# mega.net
KiCad netlist of a schematic drawn in EAGLE
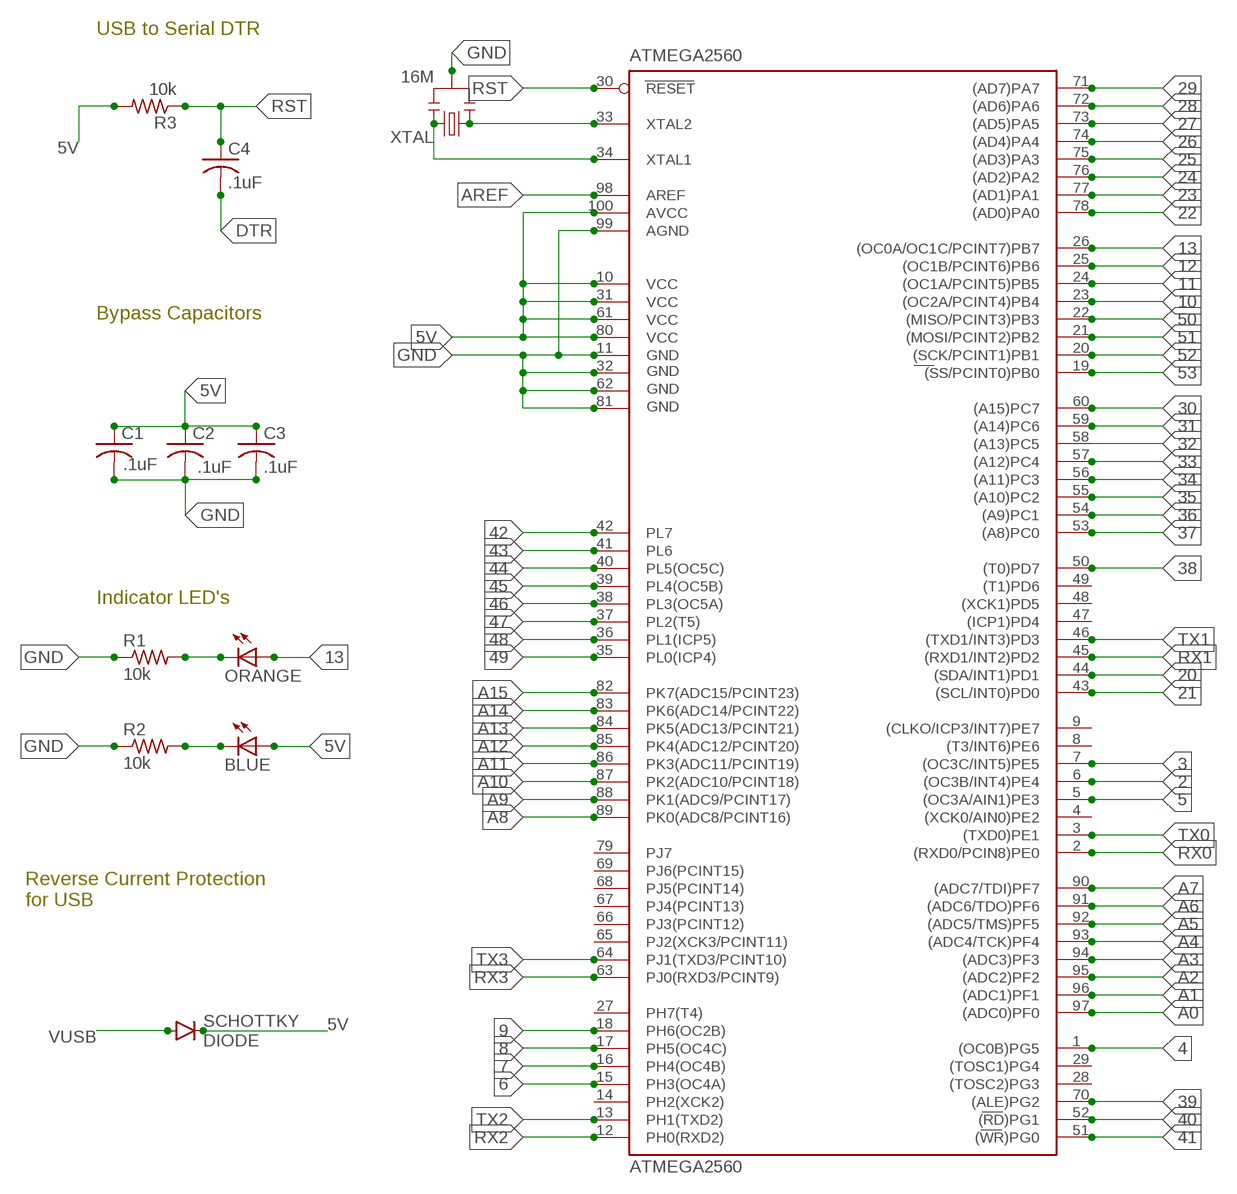
[diagram p0: schematic, sheet 1]

(export (version "E")
  (design (tool "Eeschema 10.0.6"))
  (components
    (comp (ref "ATMEGA2560")
      (value "ATMEGA2560")
      (footprint "eagle-import:TQFP100")
      (libsource (lib "eagle-import") (part "ATMEGA2560"))
    )
    (comp (ref "BLUE")
      (value "L")
      (footprint "eagle-import:SMD-0805-LED")
      (libsource (lib "eagle-import") (part "LED-SMD-0805"))
    )
    (comp (ref "C1")
      (value "CAPACITOR-SMD-0805")
      (footprint "eagle-import:SMD-0805")
      (libsource (lib "eagle-import") (part "CAPACITOR-SMD-0805"))
    )
    (comp (ref "C2")
      (value ".1uF")
      (footprint "eagle-import:SMD-0805")
      (libsource (lib "eagle-import") (part "CAPACITOR-SMD-0805"))
    )
    (comp (ref "C3")
      (value ".1uF")
      (footprint "eagle-import:SMD-0805")
      (libsource (lib "eagle-import") (part "CAPACITOR-SMD-0805"))
    )
    (comp (ref "C4")
      (value ".1uF")
      (footprint "eagle-import:SMD-0805")
      (libsource (lib "eagle-import") (part "CAPACITOR-SMD-0805"))
    )
    (comp (ref "ORANGE")
      (value "L")
      (footprint "eagle-import:SMD-0805-LED")
      (libsource (lib "eagle-import") (part "LED-SMD-0805"))
    )
    (comp (ref "R1")
      (value "10k")
      (footprint "eagle-import:SMD-0805")
      (libsource (lib "eagle-import") (part "RESISTOR-SMD-0805"))
    )
    (comp (ref "R2")
      (value "10k")
      (footprint "eagle-import:SMD-0805")
      (libsource (lib "eagle-import") (part "RESISTOR-SMD-0805"))
    )
    (comp (ref "R3")
      (value "10k")
      (footprint "eagle-import:SMD-0805")
      (libsource (lib "eagle-import") (part "RESISTOR-SMD-0805"))
    )
    (comp (ref "SCHOTTKY")
      (value "DIODE")
      (footprint "eagle-import:SOD-323")
      (libsource (lib "eagle-import") (part "DIODE"))
    )
    (comp (ref "XTAL")
      (value "16M")
      (footprint "eagle-import:RESONATOR")
      (libsource (lib "eagle-import") (part "RESONATOR"))
    )
  )
  (nets
    (net (code "1") (name "/VUSB") (class "Default")
      (node (ref "SCHOTTKY") (pin "A") (pinfunction "A_A") (pintype "passive"))
    )
    (net (code "2") (name "2") (class "Default")
      (node (ref "ATMEGA2560") (pin "6") (pinfunction "(OC3B/INT4)PE4_6") (pintype "bidirectional"))
    )
    (net (code "3") (name "3") (class "Default")
      (node (ref "ATMEGA2560") (pin "7") (pinfunction "(OC3C/INT5)PE5_7") (pintype "bidirectional"))
    )
    (net (code "4") (name "4") (class "Default")
      (node (ref "ATMEGA2560") (pin "1") (pinfunction "(OC0B)PG5_1") (pintype "bidirectional"))
    )
    (net (code "5") (name "5") (class "Default")
      (node (ref "ATMEGA2560") (pin "5") (pinfunction "(OC3A/AIN1)PE3_5") (pintype "bidirectional"))
    )
    (net (code "6") (name "5V") (class "Default")
      (node (ref "ATMEGA2560") (pin "10") (pinfunction "VCC_10") (pintype "power_in"))
      (node (ref "ATMEGA2560") (pin "100") (pinfunction "AVCC_100") (pintype "power_in"))
      (node (ref "ATMEGA2560") (pin "31") (pinfunction "VCC1_31") (pintype "power_in"))
      (node (ref "ATMEGA2560") (pin "61") (pinfunction "VCC2_61") (pintype "power_in"))
      (node (ref "ATMEGA2560") (pin "80") (pinfunction "VCC3_80") (pintype "power_in"))
      (node (ref "BLUE") (pin "1") (pinfunction "A_1") (pintype "passive"))
      (node (ref "C1") (pin "1") (pinfunction "1_1") (pintype "passive"))
      (node (ref "C2") (pin "1") (pinfunction "1_1") (pintype "passive"))
      (node (ref "C3") (pin "1") (pinfunction "1_1") (pintype "passive"))
      (node (ref "R3") (pin "2") (pinfunction "2_2") (pintype "passive"))
      (node (ref "SCHOTTKY") (pin "C") (pinfunction "C_C") (pintype "passive"))
    )
    (net (code "7") (name "6") (class "Default")
      (node (ref "ATMEGA2560") (pin "15") (pinfunction "PH3(OC4A)_15") (pintype "bidirectional"))
    )
    (net (code "8") (name "7") (class "Default")
      (node (ref "ATMEGA2560") (pin "16") (pinfunction "PH4(OC4B)_16") (pintype "bidirectional"))
    )
    (net (code "9") (name "8") (class "Default")
      (node (ref "ATMEGA2560") (pin "17") (pinfunction "PH5(OC4C)_17") (pintype "bidirectional"))
    )
    (net (code "10") (name "9") (class "Default")
      (node (ref "ATMEGA2560") (pin "18") (pinfunction "PH6(OC2B)_18") (pintype "bidirectional"))
    )
    (net (code "11") (name "10") (class "Default")
      (node (ref "ATMEGA2560") (pin "23") (pinfunction "(OC2A/PCINT4)PB4_23") (pintype "bidirectional"))
    )
    (net (code "12") (name "11") (class "Default")
      (node (ref "ATMEGA2560") (pin "24") (pinfunction "(OC1A/PCINT5)PB5_24") (pintype "bidirectional"))
    )
    (net (code "13") (name "12") (class "Default")
      (node (ref "ATMEGA2560") (pin "25") (pinfunction "(OC1B/PCINT6)PB6_25") (pintype "bidirectional"))
    )
    (net (code "14") (name "13") (class "Default")
      (node (ref "ATMEGA2560") (pin "26") (pinfunction "(OC0A/OC1C/PCINT7)PB7_26") (pintype "bidirectional"))
      (node (ref "ORANGE") (pin "1") (pinfunction "A_1") (pintype "passive"))
    )
    (net (code "15") (name "20") (class "Default")
      (node (ref "ATMEGA2560") (pin "44") (pinfunction "(SDA/INT1)PD1_44") (pintype "bidirectional"))
    )
    (net (code "16") (name "21") (class "Default")
      (node (ref "ATMEGA2560") (pin "43") (pinfunction "(SCL/INT0)PD0_43") (pintype "bidirectional"))
    )
    (net (code "17") (name "22") (class "Default")
      (node (ref "ATMEGA2560") (pin "78") (pinfunction "(AD0)PA0_78") (pintype "bidirectional"))
    )
    (net (code "18") (name "23") (class "Default")
      (node (ref "ATMEGA2560") (pin "77") (pinfunction "(AD1)PA1_77") (pintype "bidirectional"))
    )
    (net (code "19") (name "24") (class "Default")
      (node (ref "ATMEGA2560") (pin "76") (pinfunction "(AD2)PA2_76") (pintype "bidirectional"))
    )
    (net (code "20") (name "25") (class "Default")
      (node (ref "ATMEGA2560") (pin "75") (pinfunction "(AD3)PA3_75") (pintype "bidirectional"))
    )
    (net (code "21") (name "26") (class "Default")
      (node (ref "ATMEGA2560") (pin "74") (pinfunction "(AD4)PA4_74") (pintype "bidirectional"))
    )
    (net (code "22") (name "27") (class "Default")
      (node (ref "ATMEGA2560") (pin "73") (pinfunction "(AD5)PA5_73") (pintype "bidirectional"))
    )
    (net (code "23") (name "28") (class "Default")
      (node (ref "ATMEGA2560") (pin "72") (pinfunction "(AD6)PA6_72") (pintype "bidirectional"))
    )
    (net (code "24") (name "29") (class "Default")
      (node (ref "ATMEGA2560") (pin "71") (pinfunction "(AD7)PA7_71") (pintype "bidirectional"))
    )
    (net (code "25") (name "30") (class "Default")
      (node (ref "ATMEGA2560") (pin "60") (pinfunction "(A15)PC7_60") (pintype "bidirectional"))
    )
    (net (code "26") (name "31") (class "Default")
      (node (ref "ATMEGA2560") (pin "59") (pinfunction "(A14)PC6_59") (pintype "bidirectional"))
    )
    (net (code "27") (name "32") (class "Default")
      (node (ref "ATMEGA2560") (pin "58") (pinfunction "(A13)PC5_58") (pintype "bidirectional"))
    )
    (net (code "28") (name "33") (class "Default")
      (node (ref "ATMEGA2560") (pin "57") (pinfunction "(A12)PC4_57") (pintype "bidirectional"))
    )
    (net (code "29") (name "34") (class "Default")
      (node (ref "ATMEGA2560") (pin "56") (pinfunction "(A11)PC3_56") (pintype "bidirectional"))
    )
    (net (code "30") (name "35") (class "Default")
      (node (ref "ATMEGA2560") (pin "55") (pinfunction "(A10)PC2_55") (pintype "bidirectional"))
    )
    (net (code "31") (name "36") (class "Default")
      (node (ref "ATMEGA2560") (pin "54") (pinfunction "(A9)PC1_54") (pintype "bidirectional"))
    )
    (net (code "32") (name "37") (class "Default")
      (node (ref "ATMEGA2560") (pin "53") (pinfunction "(A8)PC0_53") (pintype "bidirectional"))
    )
    (net (code "33") (name "38") (class "Default")
      (node (ref "ATMEGA2560") (pin "50") (pinfunction "(T0)PD7_50") (pintype "bidirectional"))
    )
    (net (code "34") (name "39") (class "Default")
      (node (ref "ATMEGA2560") (pin "70") (pinfunction "(ALE)PG2_70") (pintype "bidirectional"))
    )
    (net (code "35") (name "40") (class "Default")
      (node (ref "ATMEGA2560") (pin "52") (pinfunction "(RD)PG1_52") (pintype "bidirectional"))
    )
    (net (code "36") (name "41") (class "Default")
      (node (ref "ATMEGA2560") (pin "51") (pinfunction "(WR)PG0_51") (pintype "bidirectional"))
    )
    (net (code "37") (name "42") (class "Default")
      (node (ref "ATMEGA2560") (pin "42") (pinfunction "PL7_42") (pintype "bidirectional"))
    )
    (net (code "38") (name "43") (class "Default")
      (node (ref "ATMEGA2560") (pin "41") (pinfunction "PL6_41") (pintype "bidirectional"))
    )
    (net (code "39") (name "44") (class "Default")
      (node (ref "ATMEGA2560") (pin "40") (pinfunction "PL5(OC5C)_40") (pintype "bidirectional"))
    )
    (net (code "40") (name "45") (class "Default")
      (node (ref "ATMEGA2560") (pin "39") (pinfunction "PL4(OC5B)_39") (pintype "bidirectional"))
    )
    (net (code "41") (name "46") (class "Default")
      (node (ref "ATMEGA2560") (pin "38") (pinfunction "PL3(OC5A)_38") (pintype "bidirectional"))
    )
    (net (code "42") (name "47") (class "Default")
      (node (ref "ATMEGA2560") (pin "37") (pinfunction "PL2(T5)_37") (pintype "bidirectional"))
    )
    (net (code "43") (name "48") (class "Default")
      (node (ref "ATMEGA2560") (pin "36") (pinfunction "PL1(ICP5)_36") (pintype "bidirectional"))
    )
    (net (code "44") (name "49") (class "Default")
      (node (ref "ATMEGA2560") (pin "35") (pinfunction "PL0(ICP4)_35") (pintype "bidirectional"))
    )
    (net (code "45") (name "50") (class "Default")
      (node (ref "ATMEGA2560") (pin "22") (pinfunction "(MISO/PCINT3)PB3_22") (pintype "bidirectional"))
    )
    (net (code "46") (name "51") (class "Default")
      (node (ref "ATMEGA2560") (pin "21") (pinfunction "(MOSI/PCINT2)PB2_21") (pintype "bidirectional"))
    )
    (net (code "47") (name "52") (class "Default")
      (node (ref "ATMEGA2560") (pin "20") (pinfunction "(SCK/PCINT1)PB1_20") (pintype "bidirectional"))
    )
    (net (code "48") (name "53") (class "Default")
      (node (ref "ATMEGA2560") (pin "19") (pinfunction "(SS/PCINT0)PB0_19") (pintype "bidirectional"))
    )
    (net (code "49") (name "A0") (class "Default")
      (node (ref "ATMEGA2560") (pin "97") (pinfunction "(ADC0)PF0_97") (pintype "bidirectional"))
    )
    (net (code "50") (name "A1") (class "Default")
      (node (ref "ATMEGA2560") (pin "96") (pinfunction "(ADC1)PF1_96") (pintype "bidirectional"))
    )
    (net (code "51") (name "A2") (class "Default")
      (node (ref "ATMEGA2560") (pin "95") (pinfunction "(ADC2)PF2_95") (pintype "bidirectional"))
    )
    (net (code "52") (name "A3") (class "Default")
      (node (ref "ATMEGA2560") (pin "94") (pinfunction "(ADC3)PF3_94") (pintype "bidirectional"))
    )
    (net (code "53") (name "A4") (class "Default")
      (node (ref "ATMEGA2560") (pin "93") (pinfunction "(ADC4/TCK)PF4_93") (pintype "bidirectional"))
    )
    (net (code "54") (name "A5") (class "Default")
      (node (ref "ATMEGA2560") (pin "92") (pinfunction "(ADC5/TMS)PF5_92") (pintype "bidirectional"))
    )
    (net (code "55") (name "A6") (class "Default")
      (node (ref "ATMEGA2560") (pin "91") (pinfunction "(ADC6/TDO)PF6_91") (pintype "bidirectional"))
    )
    (net (code "56") (name "A7") (class "Default")
      (node (ref "ATMEGA2560") (pin "90") (pinfunction "(ADC7/TDI)PF7_90") (pintype "bidirectional"))
    )
    (net (code "57") (name "A8") (class "Default")
      (node (ref "ATMEGA2560") (pin "89") (pinfunction "PK0(ADC8/PCINT16)_89") (pintype "bidirectional"))
    )
    (net (code "58") (name "A9") (class "Default")
      (node (ref "ATMEGA2560") (pin "88") (pinfunction "PK1(ADC9/PCINT17)_88") (pintype "bidirectional"))
    )
    (net (code "59") (name "A10") (class "Default")
      (node (ref "ATMEGA2560") (pin "87") (pinfunction "PK2(ADC10/PCINT18)_87") (pintype "bidirectional"))
    )
    (net (code "60") (name "A11") (class "Default")
      (node (ref "ATMEGA2560") (pin "86") (pinfunction "PK3(ADC11/PCINT19)_86") (pintype "bidirectional"))
    )
    (net (code "61") (name "A12") (class "Default")
      (node (ref "ATMEGA2560") (pin "85") (pinfunction "PK4(ADC12/PCINT20)_85") (pintype "bidirectional"))
    )
    (net (code "62") (name "A13") (class "Default")
      (node (ref "ATMEGA2560") (pin "84") (pinfunction "PK5(ADC13/PCINT21)_84") (pintype "bidirectional"))
    )
    (net (code "63") (name "A14") (class "Default")
      (node (ref "ATMEGA2560") (pin "83") (pinfunction "PK6(ADC14/PCINT22)_83") (pintype "bidirectional"))
    )
    (net (code "64") (name "A15") (class "Default")
      (node (ref "ATMEGA2560") (pin "82") (pinfunction "PK7(ADC15/PCINT23)_82") (pintype "bidirectional"))
    )
    (net (code "65") (name "AREF") (class "Default")
      (node (ref "ATMEGA2560") (pin "98") (pinfunction "AREF_98") (pintype "bidirectional"))
    )
    (net (code "66") (name "DTR") (class "Default")
      (node (ref "C4") (pin "2") (pinfunction "2_2") (pintype "passive"))
    )
    (net (code "67") (name "GND") (class "Default")
      (node (ref "ATMEGA2560") (pin "11") (pinfunction "GND_11") (pintype "power_in"))
      (node (ref "ATMEGA2560") (pin "32") (pinfunction "GND1_32") (pintype "power_in"))
      (node (ref "ATMEGA2560") (pin "62") (pinfunction "GND2_62") (pintype "power_in"))
      (node (ref "ATMEGA2560") (pin "81") (pinfunction "GND3_81") (pintype "power_in"))
      (node (ref "ATMEGA2560") (pin "99") (pinfunction "AGND_99") (pintype "power_in"))
      (node (ref "C1") (pin "2") (pinfunction "2_2") (pintype "passive"))
      (node (ref "C2") (pin "2") (pinfunction "2_2") (pintype "passive"))
      (node (ref "C3") (pin "2") (pinfunction "2_2") (pintype "passive"))
      (node (ref "R1") (pin "1") (pinfunction "1_1") (pintype "passive"))
      (node (ref "R2") (pin "1") (pinfunction "1_1") (pintype "passive"))
      (node (ref "XTAL") (pin "2") (pinfunction "2_2") (pintype "passive"))
    )
    (net (code "68") (name "Net-(ATMEGA2560-XTAL1)") (class "Default")
      (node (ref "ATMEGA2560") (pin "34") (pinfunction "XTAL1_34") (pintype "input"))
      (node (ref "XTAL") (pin "3") (pinfunction "3_3") (pintype "passive"))
    )
    (net (code "69") (name "Net-(ATMEGA2560-XTAL2)") (class "Default")
      (node (ref "ATMEGA2560") (pin "33") (pinfunction "XTAL2_33") (pintype "output"))
      (node (ref "XTAL") (pin "1") (pinfunction "1_1") (pintype "passive"))
    )
    (net (code "70") (name "Net-(BLUE-C)") (class "Default")
      (node (ref "BLUE") (pin "2") (pinfunction "C_2") (pintype "passive"))
      (node (ref "R2") (pin "2") (pinfunction "2_2") (pintype "passive"))
    )
    (net (code "71") (name "Net-(ORANGE-C)") (class "Default")
      (node (ref "ORANGE") (pin "2") (pinfunction "C_2") (pintype "passive"))
      (node (ref "R1") (pin "2") (pinfunction "2_2") (pintype "passive"))
    )
    (net (code "72") (name "RST") (class "Default")
      (node (ref "ATMEGA2560") (pin "30") (pinfunction "RESET_30") (pintype "input"))
      (node (ref "C4") (pin "1") (pinfunction "1_1") (pintype "passive"))
      (node (ref "R3") (pin "1") (pinfunction "1_1") (pintype "passive"))
    )
    (net (code "73") (name "RX0") (class "Default")
      (node (ref "ATMEGA2560") (pin "2") (pinfunction "(RXD0/PCIN8)PE0_2") (pintype "bidirectional"))
    )
    (net (code "74") (name "RX1") (class "Default")
      (node (ref "ATMEGA2560") (pin "45") (pinfunction "(RXD1/INT2)PD2_45") (pintype "bidirectional"))
    )
    (net (code "75") (name "RX2") (class "Default")
      (node (ref "ATMEGA2560") (pin "12") (pinfunction "PH0(RXD2)_12") (pintype "bidirectional"))
    )
    (net (code "76") (name "RX3") (class "Default")
      (node (ref "ATMEGA2560") (pin "63") (pinfunction "PJ0(RXD3/PCINT9)_63") (pintype "bidirectional"))
    )
    (net (code "77") (name "TX0") (class "Default")
      (node (ref "ATMEGA2560") (pin "3") (pinfunction "(TXD0)PE1_3") (pintype "bidirectional"))
    )
    (net (code "78") (name "TX1") (class "Default")
      (node (ref "ATMEGA2560") (pin "46") (pinfunction "(TXD1/INT3)PD3_46") (pintype "bidirectional"))
    )
    (net (code "79") (name "TX2") (class "Default")
      (node (ref "ATMEGA2560") (pin "13") (pinfunction "PH1(TXD2)_13") (pintype "bidirectional"))
    )
    (net (code "80") (name "TX3") (class "Default")
      (node (ref "ATMEGA2560") (pin "64") (pinfunction "PJ1(TXD3/PCINT10)_64") (pintype "bidirectional"))
    )
    (net (code "81") (name "unconnected-(ATMEGA2560-(CLKO{slash}ICP3{slash}INT7)PE7-Pad9)") (class "Default")
      (node (ref "ATMEGA2560") (pin "9") (pinfunction "(CLKO/ICP3/INT7)PE7_9") (pintype "bidirectional"))
    )
    (net (code "82") (name "unconnected-(ATMEGA2560-(ICP1)PD4-Pad47)") (class "Default")
      (node (ref "ATMEGA2560") (pin "47") (pinfunction "(ICP1)PD4_47") (pintype "bidirectional"))
    )
    (net (code "83") (name "unconnected-(ATMEGA2560-(T1)PD6-Pad49)") (class "Default")
      (node (ref "ATMEGA2560") (pin "49") (pinfunction "(T1)PD6_49") (pintype "bidirectional"))
    )
    (net (code "84") (name "unconnected-(ATMEGA2560-(T3{slash}INT6)PE6-Pad8)") (class "Default")
      (node (ref "ATMEGA2560") (pin "8") (pinfunction "(T3/INT6)PE6_8") (pintype "bidirectional"))
    )
    (net (code "85") (name "unconnected-(ATMEGA2560-(TOSC1)PG4-Pad29)") (class "Default")
      (node (ref "ATMEGA2560") (pin "29") (pinfunction "(TOSC1)PG4_29") (pintype "bidirectional"))
    )
    (net (code "86") (name "unconnected-(ATMEGA2560-(TOSC2)PG3-Pad28)") (class "Default")
      (node (ref "ATMEGA2560") (pin "28") (pinfunction "(TOSC2)PG3_28") (pintype "bidirectional"))
    )
    (net (code "87") (name "unconnected-(ATMEGA2560-(XCK0{slash}AIN0)PE2-Pad4)") (class "Default")
      (node (ref "ATMEGA2560") (pin "4") (pinfunction "(XCK0/AIN0)PE2_4") (pintype "bidirectional"))
    )
    (net (code "88") (name "unconnected-(ATMEGA2560-(XCK1)PD5-Pad48)") (class "Default")
      (node (ref "ATMEGA2560") (pin "48") (pinfunction "(XCK1)PD5_48") (pintype "bidirectional"))
    )
    (net (code "89") (name "unconnected-(ATMEGA2560-PH2(XCK2)-Pad14)") (class "Default")
      (node (ref "ATMEGA2560") (pin "14") (pinfunction "PH2(XCK2)_14") (pintype "bidirectional"))
    )
    (net (code "90") (name "unconnected-(ATMEGA2560-PH7(T4)-Pad27)") (class "Default")
      (node (ref "ATMEGA2560") (pin "27") (pinfunction "PH7(T4)_27") (pintype "bidirectional"))
    )
    (net (code "91") (name "unconnected-(ATMEGA2560-PJ2(XCK3{slash}PCINT11)-Pad65)") (class "Default")
      (node (ref "ATMEGA2560") (pin "65") (pinfunction "PJ2(XCK3/PCINT11)_65") (pintype "bidirectional"))
    )
    (net (code "92") (name "unconnected-(ATMEGA2560-PJ3(PCINT12)-Pad66)") (class "Default")
      (node (ref "ATMEGA2560") (pin "66") (pinfunction "PJ3(PCINT12)_66") (pintype "bidirectional"))
    )
    (net (code "93") (name "unconnected-(ATMEGA2560-PJ4(PCINT13)-Pad67)") (class "Default")
      (node (ref "ATMEGA2560") (pin "67") (pinfunction "PJ4(PCINT13)_67") (pintype "bidirectional"))
    )
    (net (code "94") (name "unconnected-(ATMEGA2560-PJ5(PCINT14)-Pad68)") (class "Default")
      (node (ref "ATMEGA2560") (pin "68") (pinfunction "PJ5(PCINT14)_68") (pintype "bidirectional"))
    )
    (net (code "95") (name "unconnected-(ATMEGA2560-PJ6(PCINT15)-Pad69)") (class "Default")
      (node (ref "ATMEGA2560") (pin "69") (pinfunction "PJ6(PCINT15)_69") (pintype "bidirectional"))
    )
    (net (code "96") (name "unconnected-(ATMEGA2560-PJ7-Pad79)") (class "Default")
      (node (ref "ATMEGA2560") (pin "79") (pinfunction "PJ7_79") (pintype "bidirectional"))
    )
  )
)
